# 09_-_FTDI.net
KiCad netlist of a schematic drawn in Altium Designer
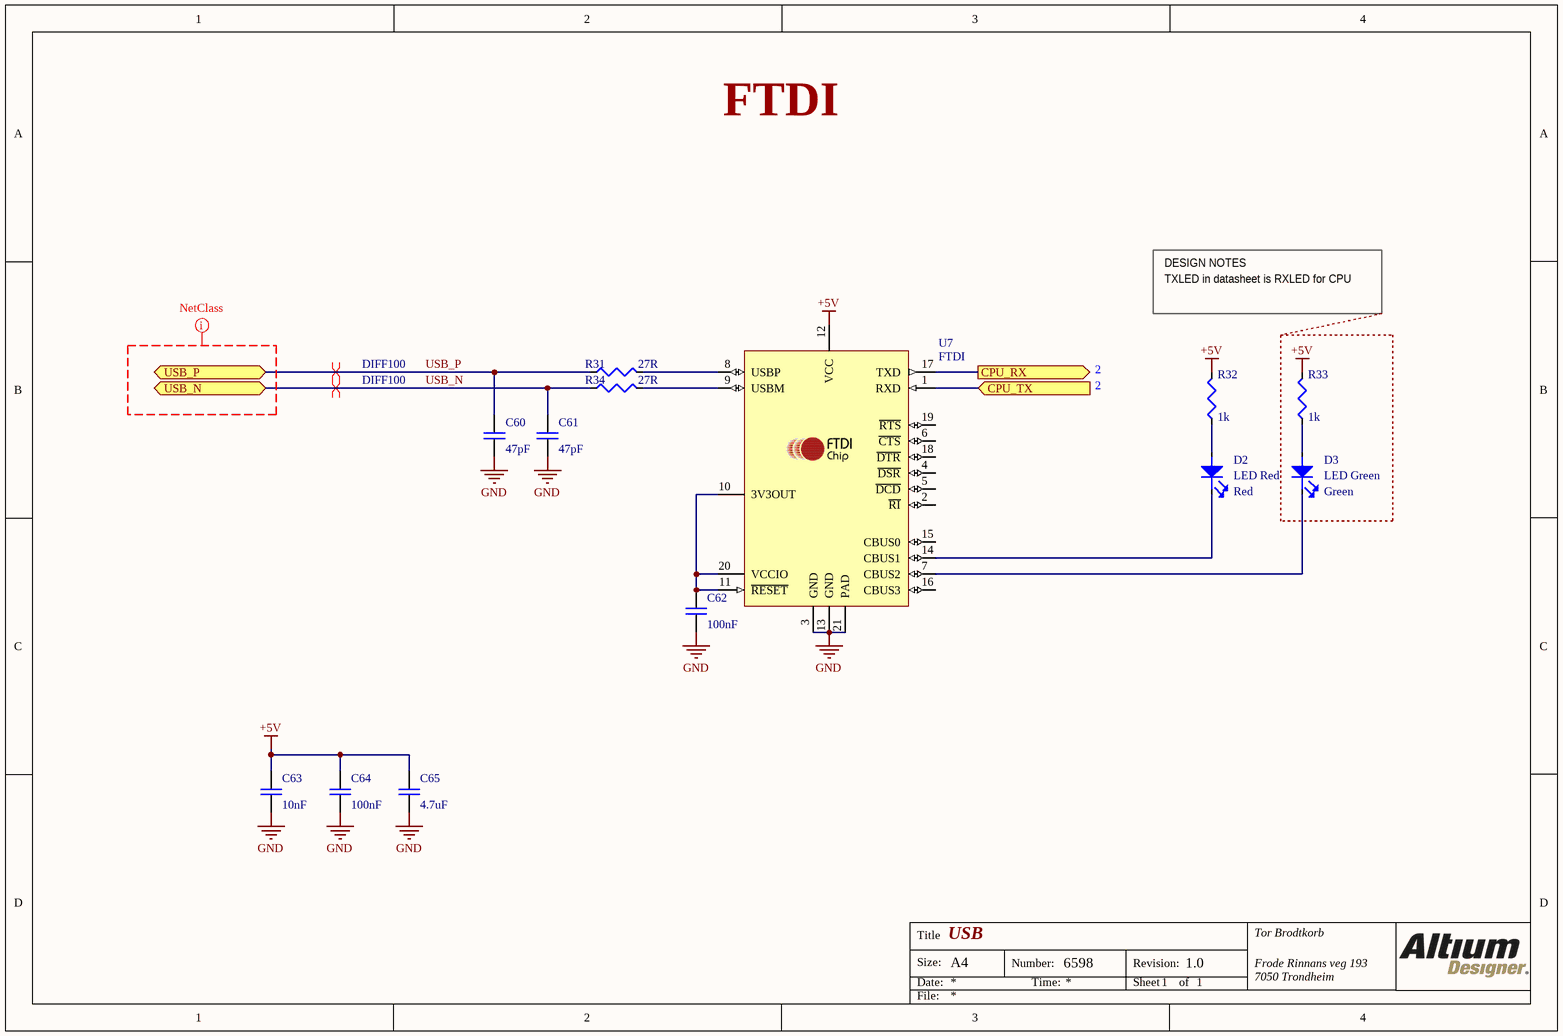
[diagram p0: [09] - FTDI.SchDoc]

(export (version "E")
  (design (tool "Eeschema 10.0.6"))
  (components
    (comp (ref "C60")
      (value "47pF")
      (footprint "C0603")
      (description "C0603")
      (fields (field (name "Comment") "02016D104KAT2A"))
      (libsource (lib "Passive components") (part "02016D104KAT2A"))
    )
    (comp (ref "C61")
      (value "47pF")
      (footprint "C0603")
      (description "C0603")
      (fields (field (name "Comment") "02016D104KAT2A"))
      (libsource (lib "Passive components") (part "02016D104KAT2A"))
    )
    (comp (ref "C62")
      (value "100nF")
      (footprint "C0603")
      (description "C0603")
      (fields (field (name "Comment") "02016D104KAT2A"))
      (libsource (lib "Passive components") (part "02016D104KAT2A"))
    )
    (comp (ref "C63")
      (value "10nF")
      (footprint "C0603")
      (description "C0603")
      (fields (field (name "Comment") "02016D104KAT2A"))
      (libsource (lib "Passive components") (part "02016D104KAT2A"))
    )
    (comp (ref "C64")
      (value "100nF")
      (footprint "C0603")
      (description "C0603")
      (fields (field (name "Comment") "02016D104KAT2A"))
      (libsource (lib "Passive components") (part "02016D104KAT2A"))
    )
    (comp (ref "C65")
      (value "4.7uF")
      (footprint "C0603")
      (description "C0603")
      (fields (field (name "Comment") "02016D104KAT2A"))
      (libsource (lib "Passive components") (part "02016D104KAT2A"))
    )
    (comp (ref "D2")
      (value "LED Red")
      (footprint "L0603 RED")
      (description "LED 0603 Red")
      (fields (field (name "COLOR") "Red"))
      (libsource (lib "Passive components") (part "HSMG-C190"))
    )
    (comp (ref "D3")
      (value "LED Green")
      (footprint "L0603 GREEN")
      (description "LED 0603 Green")
      (fields (field (name "COLOR") "Green"))
      (libsource (lib "Passive components") (part "HSMG-C196"))
    )
    (comp (ref "R31")
      (value "27R")
      (footprint "R0603")
      (description "R0603")
      (fields (field (name "Comment") "CPF-A-0603B100KE1"))
      (libsource (lib "Passive components") (part "CPF-A-0603B100KE1"))
    )
    (comp (ref "R32")
      (value "1k")
      (footprint "R0603")
      (description "R0603")
      (fields (field (name "Comment") "CPF-A-0603B100KE1"))
      (libsource (lib "Passive components") (part "CPF-A-0603B100KE1"))
    )
    (comp (ref "R33")
      (value "1k")
      (footprint "R0603")
      (description "R0603")
      (fields (field (name "Comment") "CPF-A-0603B100KE1"))
      (libsource (lib "Passive components") (part "CPF-A-0603B100KE1"))
    )
    (comp (ref "R34")
      (value "27R")
      (footprint "R0603")
      (description "R0603")
      (fields (field (name "Comment") "CPF-A-0603B100KE1"))
      (libsource (lib "Passive components") (part "CPF-A-0603B100KE1"))
    )
    (comp (ref "U7")
      (value "FTDI")
      (footprint "FT231XQ-R")
      (description "UART to USB converter")
      (libsource (lib "IC") (part "FT231XQ-R"))
    )
  )
  (nets
    (net (code "1") (name "+5V") (class "Default")
      (node (ref "C63") (pin "2") (pinfunction "2_2") (pintype "passive"))
      (node (ref "C64") (pin "2") (pinfunction "2_2") (pintype "passive"))
      (node (ref "C65") (pin "2") (pinfunction "2_2") (pintype "passive"))
      (node (ref "R32") (pin "2") (pinfunction "2_2") (pintype "passive"))
      (node (ref "R33") (pin "2") (pinfunction "2_2") (pintype "passive"))
      (node (ref "U7") (pin "12") (pinfunction "VCC_12") (pintype "passive"))
    )
    (net (code "2") (name "/CPU_RX") (class "Default")
      (node (ref "U7") (pin "17") (pinfunction "TXD_17") (pintype "output"))
    )
    (net (code "3") (name "/CPU_TX") (class "Default")
      (node (ref "U7") (pin "1") (pinfunction "RXD_1") (pintype "input"))
    )
    (net (code "4") (name "/USB_N") (class "Default")
      (node (ref "C61") (pin "2") (pinfunction "2_2") (pintype "passive"))
      (node (ref "R34") (pin "1") (pinfunction "1_1") (pintype "passive"))
    )
    (net (code "5") (name "/USB_P") (class "Default")
      (node (ref "C60") (pin "2") (pinfunction "2_2") (pintype "passive"))
      (node (ref "R31") (pin "1") (pinfunction "1_1") (pintype "passive"))
    )
    (net (code "6") (name "GND") (class "Default")
      (node (ref "C60") (pin "1") (pinfunction "1_1") (pintype "passive"))
      (node (ref "C61") (pin "1") (pinfunction "1_1") (pintype "passive"))
      (node (ref "C62") (pin "1") (pinfunction "1_1") (pintype "passive"))
      (node (ref "C63") (pin "1") (pinfunction "1_1") (pintype "passive"))
      (node (ref "C64") (pin "1") (pinfunction "1_1") (pintype "passive"))
      (node (ref "C65") (pin "1") (pinfunction "1_1") (pintype "passive"))
      (node (ref "U7") (pin "13") (pinfunction "GND_13") (pintype "passive"))
      (node (ref "U7") (pin "21") (pinfunction "PAD_21") (pintype "passive"))
      (node (ref "U7") (pin "3") (pinfunction "GND_3") (pintype "passive"))
    )
    (net (code "7") (name "Net-(D2-Pad1)") (class "Default")
      (node (ref "D2") (pin "1") (pinfunction "1_1") (pintype "passive"))
      (node (ref "R32") (pin "1") (pinfunction "1_1") (pintype "passive"))
    )
    (net (code "8") (name "Net-(D3-Pad1)") (class "Default")
      (node (ref "D3") (pin "1") (pinfunction "1_1") (pintype "passive"))
      (node (ref "R33") (pin "1") (pinfunction "1_1") (pintype "passive"))
    )
    (net (code "9") (name "Net-(U7-3V3OUT)") (class "Default")
      (node (ref "C62") (pin "2") (pinfunction "2_2") (pintype "passive"))
      (node (ref "U7") (pin "10") (pinfunction "3V3OUT_10") (pintype "passive"))
      (node (ref "U7") (pin "11") (pinfunction "~{RESET}_11") (pintype "input"))
      (node (ref "U7") (pin "20") (pinfunction "VCCIO_20") (pintype "passive"))
    )
    (net (code "10") (name "Net-(U7-CBUS1)") (class "Default")
      (node (ref "D2") (pin "2") (pinfunction "2_2") (pintype "passive"))
      (node (ref "U7") (pin "14") (pinfunction "CBUS1_14") (pintype "bidirectional"))
    )
    (net (code "11") (name "Net-(U7-CBUS2)") (class "Default")
      (node (ref "D3") (pin "2") (pinfunction "2_2") (pintype "passive"))
      (node (ref "U7") (pin "7") (pinfunction "CBUS2_7") (pintype "bidirectional"))
    )
    (net (code "12") (name "Net-(U7-USBM)") (class "Default")
      (node (ref "R34") (pin "2") (pinfunction "2_2") (pintype "passive"))
      (node (ref "U7") (pin "9") (pinfunction "USBM_9") (pintype "bidirectional"))
    )
    (net (code "13") (name "Net-(U7-USBP)") (class "Default")
      (node (ref "R31") (pin "2") (pinfunction "2_2") (pintype "passive"))
      (node (ref "U7") (pin "8") (pinfunction "USBP_8") (pintype "bidirectional"))
    )
    (net (code "14") (name "unconnected-(U7-CBUS0-Pad15)") (class "Default")
      (node (ref "U7") (pin "15") (pinfunction "CBUS0_15") (pintype "bidirectional"))
    )
    (net (code "15") (name "unconnected-(U7-CBUS3-Pad16)") (class "Default")
      (node (ref "U7") (pin "16") (pinfunction "CBUS3_16") (pintype "bidirectional"))
    )
    (net (code "16") (name "unconnected-(U7-~{CTS}-Pad6)") (class "Default")
      (node (ref "U7") (pin "6") (pinfunction "~{CTS}_6") (pintype "bidirectional"))
    )
    (net (code "17") (name "unconnected-(U7-~{DCD}-Pad5)") (class "Default")
      (node (ref "U7") (pin "5") (pinfunction "~{DCD}_5") (pintype "bidirectional"))
    )
    (net (code "18") (name "unconnected-(U7-~{DSR}-Pad4)") (class "Default")
      (node (ref "U7") (pin "4") (pinfunction "~{DSR}_4") (pintype "bidirectional"))
    )
    (net (code "19") (name "unconnected-(U7-~{DTR}-Pad18)") (class "Default")
      (node (ref "U7") (pin "18") (pinfunction "~{DTR}_18") (pintype "bidirectional"))
    )
    (net (code "20") (name "unconnected-(U7-~{RI}-Pad2)") (class "Default")
      (node (ref "U7") (pin "2") (pinfunction "~{RI}_2") (pintype "bidirectional"))
    )
    (net (code "21") (name "unconnected-(U7-~{RTS}-Pad19)") (class "Default")
      (node (ref "U7") (pin "19") (pinfunction "~{RTS}_19") (pintype "bidirectional"))
    )
  )
)
